# lm3410-sepic-led-driver-16mm-mk-2.net
KiCad netlist of a schematic drawn in EAGLE
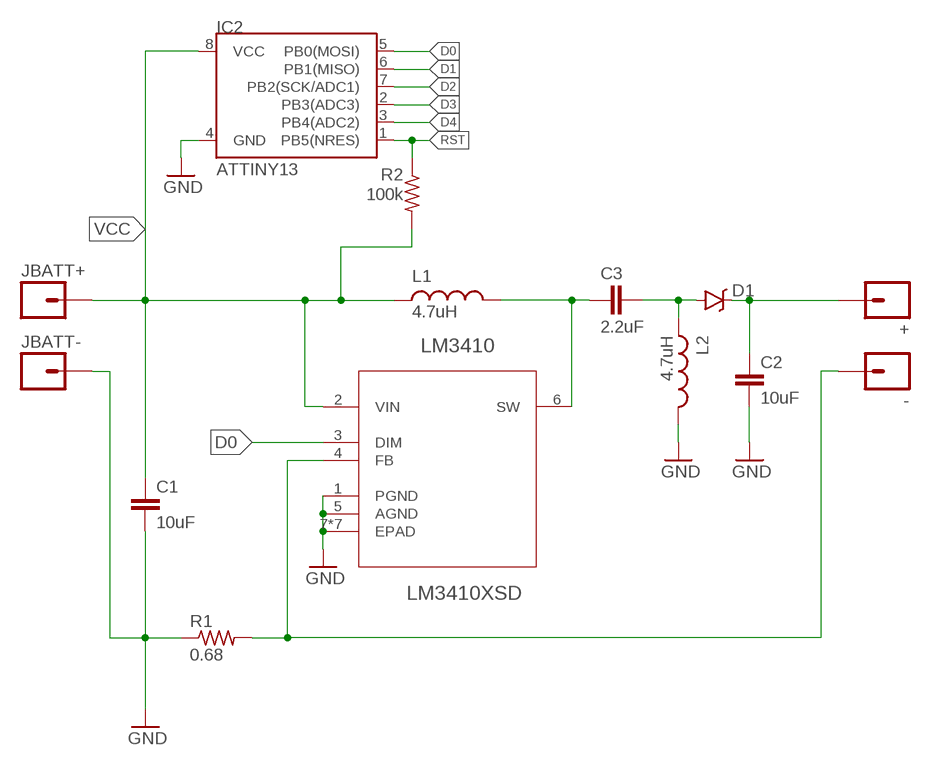
[diagram p0: schematic, sheet 1]

(export (version "E")
  (design (tool "Eeschema 10.0.6"))
  (components
    (comp (ref "+")
      (value "M01PTH-KIT")
      (footprint "eagle-import:1X01-KIT")
      (libsource (lib "eagle-import") (part "M01PTH-KIT"))
    )
    (comp (ref "-")
      (value "M01NOSILK-KIT")
      (footprint "eagle-import:1X01NS-KIT")
      (libsource (lib "eagle-import") (part "M01NOSILK-KIT"))
    )
    (comp (ref "C1")
      (value "10uF")
      (footprint "eagle-import:C0603")
      (libsource (lib "eagle-import") (part "CAPACITOR-CERAMICC0603"))
    )
    (comp (ref "C2")
      (value "10uF")
      (footprint "eagle-import:C0603")
      (libsource (lib "eagle-import") (part "CAPACITOR-CERAMICC0603"))
    )
    (comp (ref "C3")
      (value "2.2uF")
      (footprint "eagle-import:C0805")
      (libsource (lib "eagle-import") (part "CAPACITOR-CERAMICC0805"))
    )
    (comp (ref "D1")
      (value "BAT20J")
      (footprint "eagle-import:SOD-323")
      (libsource (lib "eagle-import") (part "DIODE-SCHOTTKYBAT20J"))
    )
    (comp (ref "IC2")
      (value "ATTINY13")
      (footprint "eagle-import:SO08")
      (libsource (lib "eagle-import") (part "ATTINY13SOIC"))
    )
    (comp (ref "JBATT+")
      (value "M01NOT-A-VIA-NOPE")
      (footprint "eagle-import:1X01_NOSILK_NOSTOP")
      (libsource (lib "eagle-import") (part "M01NOT-A-VIA-NOPE"))
    )
    (comp (ref "JBATT-")
      (value "M01NOT-A-VIA-NOPE")
      (footprint "eagle-import:1X01_NOSILK_NOSTOP")
      (libsource (lib "eagle-import") (part "M01NOT-A-VIA-NOPE"))
    )
    (comp (ref "L1")
      (value "4.7uH")
      (footprint "eagle-import:INDUCTOR_2X1.6MM")
      (libsource (lib "eagle-import") (part "INDUCTORIFSC-0806"))
    )
    (comp (ref "L2")
      (value "4.7uH")
      (footprint "eagle-import:INDUCTOR_2X1.6MM")
      (libsource (lib "eagle-import") (part "INDUCTORIFSC-0806"))
    )
    (comp (ref "LM3410")
      (value "LM3410XSD")
      (footprint "eagle-import:DFN300X300X80-7N")
      (libsource (lib "eagle-import") (part "LM3410XSD"))
    )
    (comp (ref "R1")
      (value "0.68")
      (footprint "eagle-import:R1206")
      (libsource (lib "eagle-import") (part "RESISTORR1206"))
    )
    (comp (ref "R2")
      (value "100k")
      (footprint "eagle-import:R0402")
      (libsource (lib "eagle-import") (part "RESISTORR0402"))
    )
  )
  (nets
    (net (code "1") (name "D0") (class "Default")
      (node (ref "IC2") (pin "5") (pinfunction "PB0(MOSI)_5") (pintype "bidirectional"))
      (node (ref "LM3410") (pin "3") (pinfunction "DIM_3") (pintype "input"))
    )
    (net (code "2") (name "D1") (class "Default")
      (node (ref "IC2") (pin "6") (pinfunction "PB1(MISO)_6") (pintype "bidirectional"))
    )
    (net (code "3") (name "D2") (class "Default")
      (node (ref "IC2") (pin "7") (pinfunction "PB2(SCK/ADC1)_7") (pintype "bidirectional"))
    )
    (net (code "4") (name "D3") (class "Default")
      (node (ref "IC2") (pin "2") (pinfunction "PB3(ADC3)_2") (pintype "bidirectional"))
    )
    (net (code "5") (name "D4") (class "Default")
      (node (ref "IC2") (pin "3") (pinfunction "PB4(ADC2)_3") (pintype "bidirectional"))
    )
    (net (code "6") (name "GND") (class "Default")
      (node (ref "C1") (pin "2") (pinfunction "2_2") (pintype "passive"))
      (node (ref "C2") (pin "2") (pinfunction "2_2") (pintype "passive"))
      (node (ref "IC2") (pin "4") (pinfunction "GND_4") (pintype "bidirectional"))
      (node (ref "JBATT-") (pin "P$1") (pinfunction "1_P$1") (pintype "passive"))
      (node (ref "L2") (pin "P$2") (pinfunction "2_P$2") (pintype "passive"))
      (node (ref "LM3410") (pin "1") (pinfunction "PGND_1") (pintype "passive"))
      (node (ref "LM3410") (pin "5") (pinfunction "AGND_5") (pintype "passive"))
      (node (ref "LM3410") (pin "7") (pinfunction "EPAD_7") (pintype "passive"))
      (node (ref "LM3410") (pin "7@1") (pinfunction "EPAD_7@1") (pintype "passive"))
      (node (ref "LM3410") (pin "7@2") (pinfunction "EPAD_7@2") (pintype "passive"))
      (node (ref "LM3410") (pin "7@3") (pinfunction "EPAD_7@3") (pintype "passive"))
      (node (ref "LM3410") (pin "7@4") (pinfunction "EPAD_7@4") (pintype "passive"))
      (node (ref "LM3410") (pin "7@5") (pinfunction "EPAD_7@5") (pintype "passive"))
      (node (ref "LM3410") (pin "7@6") (pinfunction "EPAD_7@6") (pintype "passive"))
      (node (ref "R1") (pin "1") (pinfunction "1_1") (pintype "passive"))
    )
    (net (code "7") (name "Net-(+-Pad1)") (class "Default")
      (node (ref "+") (pin "1") (pinfunction "1_1") (pintype "passive"))
      (node (ref "C2") (pin "1") (pinfunction "1_1") (pintype "passive"))
      (node (ref "D1") (pin "C") (pinfunction "C_C") (pintype "passive"))
    )
    (net (code "8") (name "Net-(L1-2)") (class "Default")
      (node (ref "C3") (pin "1") (pinfunction "1_1") (pintype "passive"))
      (node (ref "L1") (pin "P$2") (pinfunction "2_P$2") (pintype "passive"))
      (node (ref "LM3410") (pin "6") (pinfunction "SW_6") (pintype "output"))
    )
    (net (code "9") (name "Net-(L2-1)") (class "Default")
      (node (ref "C3") (pin "2") (pinfunction "2_2") (pintype "passive"))
      (node (ref "D1") (pin "A") (pinfunction "A_A") (pintype "passive"))
      (node (ref "L2") (pin "P$1") (pinfunction "1_P$1") (pintype "passive"))
    )
    (net (code "10") (name "Net-(LM3410-FB)") (class "Default")
      (node (ref "-") (pin "1") (pinfunction "1_1") (pintype "passive"))
      (node (ref "LM3410") (pin "4") (pinfunction "FB_4") (pintype "input"))
      (node (ref "R1") (pin "2") (pinfunction "2_2") (pintype "passive"))
    )
    (net (code "11") (name "RST") (class "Default")
      (node (ref "IC2") (pin "1") (pinfunction "PB5(NRES)_1") (pintype "bidirectional"))
      (node (ref "R2") (pin "1") (pinfunction "1_1") (pintype "passive"))
    )
    (net (code "12") (name "VCC") (class "Default")
      (node (ref "C1") (pin "1") (pinfunction "1_1") (pintype "passive"))
      (node (ref "IC2") (pin "8") (pinfunction "VCC_8") (pintype "bidirectional"))
      (node (ref "JBATT+") (pin "P$1") (pinfunction "1_P$1") (pintype "passive"))
      (node (ref "L1") (pin "P$1") (pinfunction "1_P$1") (pintype "passive"))
      (node (ref "LM3410") (pin "2") (pinfunction "VIN_2") (pintype "power_in"))
      (node (ref "R2") (pin "2") (pinfunction "2_2") (pintype "passive"))
    )
  )
)
